# 13-JLINK_2.net
KiCad netlist of a schematic drawn in Altium Designer
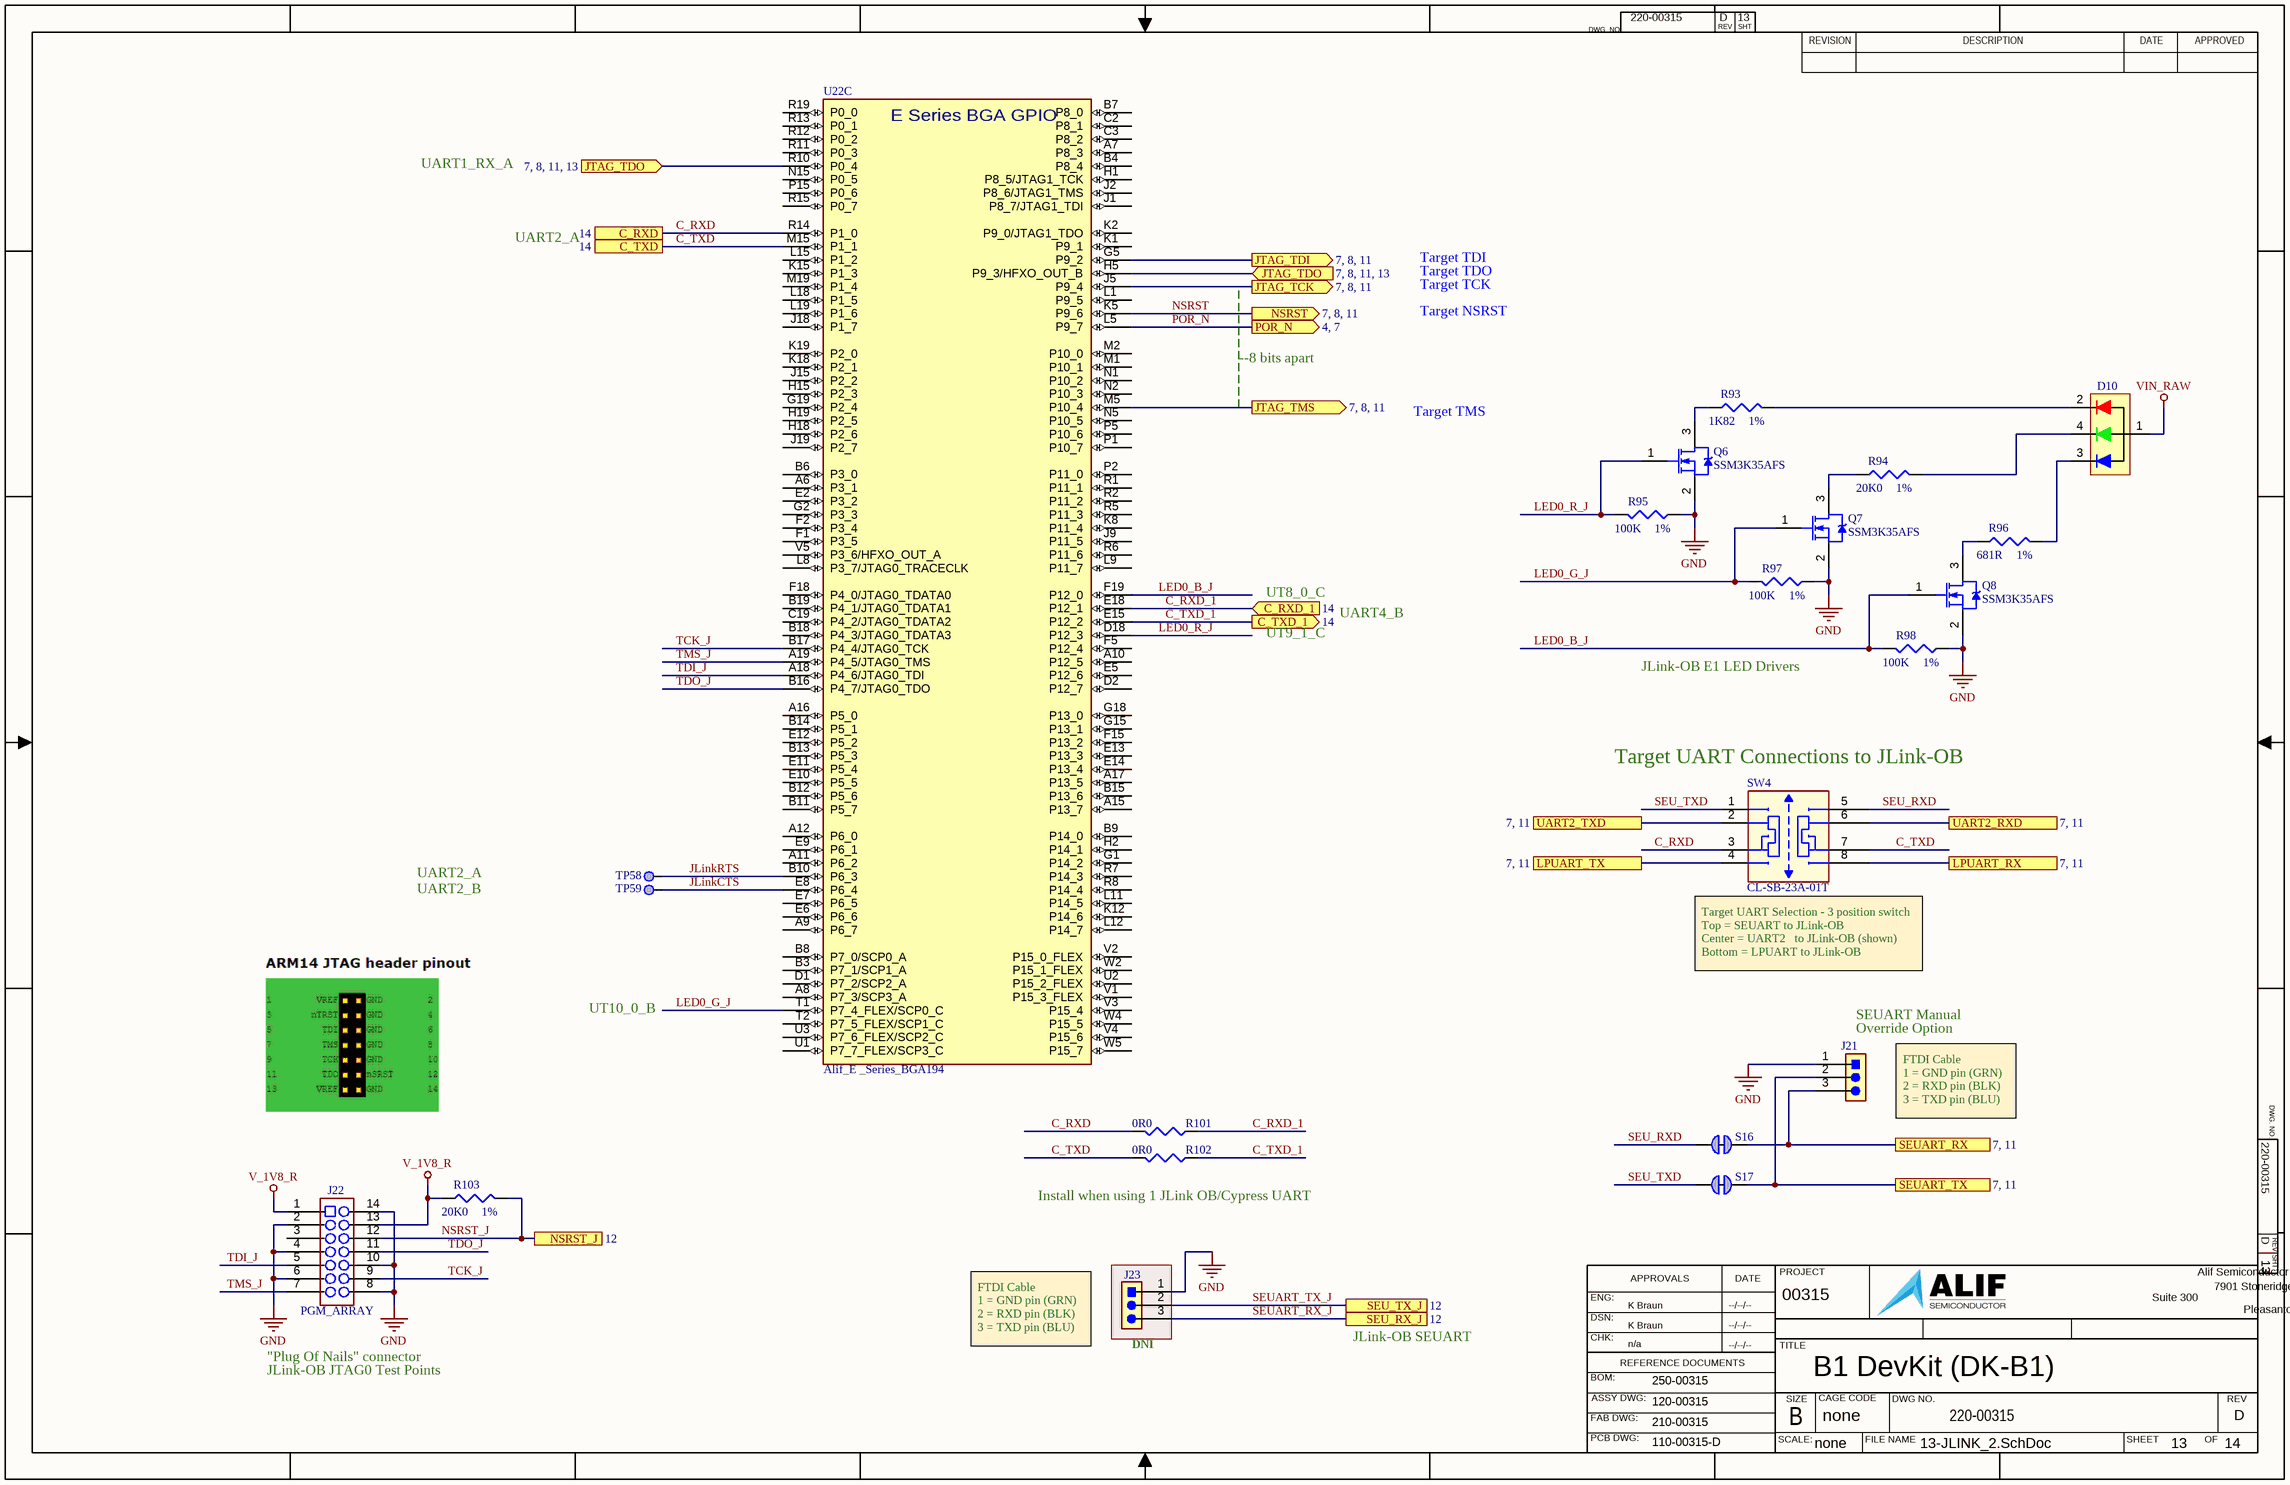
[diagram p0: 13-JLINK_2.SchDoc]

(export (version "E")
  (design (tool "Eeschema 10.0.6"))
  (components
    (comp (ref "D10")
      (value "SML-LX0404SIUPGUSB")
      (footprint "LED_SML-LX0404_LUM")
      (description "Diode,LED,RGB, (@2mA) -> R=10mcd & 1.75V, G = 50mcd & 2.75V, B = 20mcd & 2.95V, 0404(1mm x 1mm)")
      (fields (field (name "PUBLISHER") "Altium Limited"))
      (libsource (lib "Alif-2") (part "D LED_RGB_CA_1MMc1MM"))
    )
    (comp (ref "J21")
      (value "TSW-103-07-G-S")
      (footprint "CONN_HDR_1X3_STRT_0.100_no3D")
      (fields (field (name "MANUFACTURER") "Samtec"))
      (libsource (lib "") (part "Hdr_M_1X3_2M54_STRT_UNSHROUD_1"))
    )
    (comp (ref "J22")
      (value "PGM_ARRAY")
      (footprint "TC2070-IDC")
      (description "Test Point, Array, Alignment Pins, SMT Pad,--not a BOM item--")
      (fields (field (name "Comment") "PGMG_CONTACT,14P,TC2070-IDC_1"))
      (libsource (lib "Alif-2") (part "PGMG_CONTACT,14P,TC2070-IDC_1"))
    )
    (comp (ref "J23")
      (value "TSW-103-07-G-S")
      (footprint "CONN_HDR_1X3_STRT_0.100_no3D")
      (fields (field (name "MANUFACTURER") "Samtec"))
      (libsource (lib "Alif-2") (part "Hdr_M_1X3_2M54_STRT_UNSHROUD"))
    )
    (comp (ref "Q6")
      (value "NMOS-2_SOT")
      (footprint "SC75_SSM_TOS-L")
      (description "MOSFET,N-CH,20V,250mA,1.1Ohm,SOT-23")
      (fields
        (field (name "MANUFACTURER PART NUMBER 1") "SSM3K35AFS")
        (field (name "PUBLISHER") "Altium Limited")
      )
      (libsource (lib "Alif-2") (part "NMOS-2_SOT"))
    )
    (comp (ref "Q7")
      (value "NMOS-2_SOT")
      (footprint "SC75_SSM_TOS-L")
      (description "MOSFET,N-CH,20V,250mA,1.1Ohm,SOT-23")
      (fields
        (field (name "MANUFACTURER PART NUMBER 1") "SSM3K35AFS")
        (field (name "PUBLISHER") "Altium Limited")
      )
      (libsource (lib "Alif-2") (part "NMOS-2_SOT"))
    )
    (comp (ref "Q8")
      (value "NMOS-2_SOT")
      (footprint "SC75_SSM_TOS-L")
      (description "MOSFET,N-CH,20V,250mA,1.1Ohm,SOT-23")
      (fields
        (field (name "MANUFACTURER PART NUMBER 1") "SSM3K35AFS")
        (field (name "PUBLISHER") "Altium Limited")
      )
      (libsource (lib "Alif-2") (part "NMOS-2_SOT"))
    )
    (comp (ref "R93")
      (value "1K82")
      (footprint "RESC0402-01")
      (description "Res,1K82,1%,100ppm,0402")
      (fields
        (field (name "TOLERANCE") "1%")
        (field (name "Comment") "Res3")
        (field (name "PUBLISHER") "Altium Limited")
      )
      (libsource (lib "kb1") (part "Res3"))
    )
    (comp (ref "R94")
      (value "20K0")
      (footprint "RESC0402-01")
      (description "Res,20K0,1%,100ppm,0402")
      (fields
        (field (name "TOLERANCE") "1%")
        (field (name "Comment") "Res3")
        (field (name "PUBLISHER") "Altium Limited")
      )
      (libsource (lib "kb1") (part "Res3"))
    )
    (comp (ref "R95")
      (value "100K")
      (footprint "RESC0402-01")
      (description "Res,100K,1%,100ppm,0402")
      (fields
        (field (name "TOLERANCE") "1%")
        (field (name "Comment") "Res3")
        (field (name "PUBLISHER") "Altium Limited")
      )
      (libsource (lib "kb1") (part "Res3"))
    )
    (comp (ref "R96")
      (value "681R")
      (footprint "RESC0402-01")
      (description "Res,681R,1%,100ppm,0402")
      (fields
        (field (name "TOLERANCE") "1%")
        (field (name "Comment") "Res3")
        (field (name "PUBLISHER") "Altium Limited")
      )
      (libsource (lib "kb1") (part "Res3"))
    )
    (comp (ref "R97")
      (value "100K")
      (footprint "RESC0402-01")
      (description "Res,100K,1%,100ppm,0402")
      (fields
        (field (name "TOLERANCE") "1%")
        (field (name "Comment") "Res3")
        (field (name "PUBLISHER") "Altium Limited")
      )
      (libsource (lib "kb1") (part "Res3"))
    )
    (comp (ref "R98")
      (value "100K")
      (footprint "RESC0402-01")
      (description "Res,100K,1%,100ppm,0402")
      (fields
        (field (name "TOLERANCE") "1%")
        (field (name "Comment") "Res3")
        (field (name "PUBLISHER") "Altium Limited")
      )
      (libsource (lib "kb1") (part "Res3"))
    )
    (comp (ref "R101")
      (value "0R0")
      (footprint "RESC0402-01")
      (description "Res,0R ohm,Jumper,0402")
      (fields
        (field (name "TOLERANCE") "JMPR")
        (field (name "Comment") "Res3")
        (field (name "PUBLISHER") "Altium Limited")
      )
      (libsource (lib "kb1") (part "Res3"))
    )
    (comp (ref "R102")
      (value "0R0")
      (footprint "RESC0402-01")
      (description "Res,0R ohm,Jumper,0402")
      (fields
        (field (name "TOLERANCE") "JMPR")
        (field (name "Comment") "Res3")
        (field (name "PUBLISHER") "Altium Limited")
      )
      (libsource (lib "kb1") (part "Res3"))
    )
    (comp (ref "R103")
      (value "20K0")
      (footprint "RESC0402-01")
      (description "Res,20K0,1%,100ppm,0402")
      (fields
        (field (name "TOLERANCE") "1%")
        (field (name "Comment") "Res3")
        (field (name "PUBLISHER") "Altium Limited")
      )
      (libsource (lib "kb1") (part "Res3"))
    )
    (comp (ref "S16")
      (value "SolderJumperShorted_Small")
      (footprint "Solderbridge_Shorted")
      (description "DNI,Solderable Jumper,Shorted")
      (fields (field (name "PUBLISHER") "Altium Limited"))
      (libsource (lib "Alif-2") (part "SolderJumperShorted_Small"))
    )
    (comp (ref "S17")
      (value "SolderJumperShorted_Small")
      (footprint "Solderbridge_Shorted")
      (description "DNI,Solderable Jumper,Shorted")
      (fields (field (name "PUBLISHER") "Altium Limited"))
      (libsource (lib "Alif-2") (part "SolderJumperShorted_Small"))
    )
    (comp (ref "SW4")
      (value "CL-SB-23A-01T")
      (footprint "SW_CL-SB-23A-01_NDC-M")
      (description "Switch, DP3T Slide,8-pin, Vertical, 13mm x 3.6mm x 3.5mm, Actuator 2mm , Tin Contacts,JLead SMT")
      (libsource (lib "Alif-2") (part "SW_DP3T_CL-SB-23A-01T"))
    )
    (comp (ref "TP58")
      (value "TP_SMPAD")
      (footprint "TP_30_RND")
      (description "Test Point, SMT Pad,--not a BOM item--")
      (libsource (lib "Alif-2") (part "TP_SMPAD"))
    )
    (comp (ref "TP59")
      (value "TP_SMPAD")
      (footprint "TP_30_RND")
      (description "Test Point, SMT Pad,--not a BOM item--")
      (libsource (lib "Alif-2") (part "TP_SMPAD"))
    )
    (comp (ref "U22")
      (value "Alif_E _Series_BGA194")
      (footprint "BGA194 _CENTERED")
      (description "IC,Alif E1 MCU, Rev B silicon,BGA194")
      (libsource (lib "Alif") (part "E7_B0_194BGA"))
    )
  )
  (nets
    (net (code "1") (name "/C_RXD") (class "Default")
      (node (ref "R101") (pin "2") (pinfunction "2_2") (pintype "passive"))
      (node (ref "SW4") (pin "3") (pinfunction "CA_3") (pintype "passive"))
      (node (ref "U22") (pin "R14") (pinfunction "P1_0_R14") (pintype "bidirectional"))
    )
    (net (code "2") (name "/C_RXD_1") (class "Default")
      (node (ref "R101") (pin "1") (pinfunction "1_1") (pintype "passive"))
      (node (ref "U22") (pin "E18") (pinfunction "P12_1_E18") (pintype "bidirectional"))
    )
    (net (code "3") (name "/C_TXD") (class "Default")
      (node (ref "R102") (pin "2") (pinfunction "2_2") (pintype "passive"))
      (node (ref "SW4") (pin "7") (pinfunction "2B_7") (pintype "passive"))
      (node (ref "U22") (pin "M15") (pinfunction "P1_1_M15") (pintype "bidirectional"))
    )
    (net (code "4") (name "/C_TXD_1") (class "Default")
      (node (ref "R102") (pin "1") (pinfunction "1_1") (pintype "passive"))
      (node (ref "U22") (pin "E15") (pinfunction "P12_2_E15") (pintype "bidirectional"))
    )
    (net (code "5") (name "/JLinkCTS") (class "Default")
      (node (ref "TP59") (pin "1") (pinfunction "1_1") (pintype "passive"))
      (node (ref "U22") (pin "E8") (pinfunction "P6_4_E8") (pintype "bidirectional"))
    )
    (net (code "6") (name "/JLinkRTS") (class "Default")
      (node (ref "TP58") (pin "1") (pinfunction "1_1") (pintype "passive"))
      (node (ref "U22") (pin "B10") (pinfunction "P6_3_B10") (pintype "bidirectional"))
    )
    (net (code "7") (name "/JTAG_TCK") (class "Default")
      (node (ref "U22") (pin "J5") (pinfunction "P9_4_J5") (pintype "bidirectional"))
    )
    (net (code "8") (name "/JTAG_TDI") (class "Default")
      (node (ref "U22") (pin "G5") (pinfunction "P9_2_G5") (pintype "bidirectional"))
    )
    (net (code "9") (name "/JTAG_TDO") (class "Default")
      (node (ref "U22") (pin "H5") (pinfunction "P9_3/HFXO_OUT_B_H5") (pintype "bidirectional"))
      (node (ref "U22") (pin "R10") (pinfunction "P0_4_R10") (pintype "bidirectional"))
    )
    (net (code "10") (name "/JTAG_TMS") (class "Default")
      (node (ref "U22") (pin "M5") (pinfunction "P10_4_M5") (pintype "bidirectional"))
    )
    (net (code "11") (name "/LED0_B_J") (class "Default")
      (node (ref "Q8") (pin "1") (pinfunction "G_1") (pintype "passive"))
      (node (ref "R98") (pin "2") (pinfunction "2_2") (pintype "passive"))
      (node (ref "U22") (pin "F19") (pinfunction "P12_0_F19") (pintype "bidirectional"))
    )
    (net (code "12") (name "/LED0_G_J") (class "Default")
      (node (ref "Q7") (pin "1") (pinfunction "G_1") (pintype "passive"))
      (node (ref "R97") (pin "2") (pinfunction "2_2") (pintype "passive"))
      (node (ref "U22") (pin "T1") (pinfunction "P7_4_FLEX/SCP0_C_T1") (pintype "bidirectional"))
    )
    (net (code "13") (name "/LED0_R_J") (class "Default")
      (node (ref "Q6") (pin "1") (pinfunction "G_1") (pintype "passive"))
      (node (ref "R95") (pin "2") (pinfunction "2_2") (pintype "passive"))
      (node (ref "U22") (pin "D18") (pinfunction "P12_3_D18") (pintype "bidirectional"))
    )
    (net (code "14") (name "/LPUART_RX") (class "Default")
      (node (ref "SW4") (pin "8") (pinfunction "1B_8") (pintype "passive"))
    )
    (net (code "15") (name "/LPUART_TX") (class "Default")
      (node (ref "SW4") (pin "4") (pinfunction "3A_4") (pintype "passive"))
    )
    (net (code "16") (name "/NSRST") (class "Default")
      (node (ref "U22") (pin "K5") (pinfunction "P9_6_K5") (pintype "bidirectional"))
    )
    (net (code "17") (name "/NSRST_J") (class "Default")
      (node (ref "J22") (pin "12") (pinfunction "12_12") (pintype "passive"))
      (node (ref "R103") (pin "2") (pinfunction "2_2") (pintype "passive"))
    )
    (net (code "18") (name "/POR_N") (class "Default")
      (node (ref "U22") (pin "L5") (pinfunction "P9_7_L5") (pintype "bidirectional"))
    )
    (net (code "19") (name "/SEUART_RX") (class "Default")
      (node (ref "J21") (pin "3") (pinfunction "3_3") (pintype "passive"))
      (node (ref "S16") (pin "2") (pinfunction "2_2") (pintype "passive"))
    )
    (net (code "20") (name "/SEUART_RX_J") (class "Default")
      (node (ref "J23") (pin "3") (pinfunction "3_3") (pintype "passive"))
    )
    (net (code "21") (name "/SEUART_TX") (class "Default")
      (node (ref "J21") (pin "2") (pinfunction "2_2") (pintype "passive"))
      (node (ref "S17") (pin "2") (pinfunction "2_2") (pintype "passive"))
    )
    (net (code "22") (name "/SEUART_TX_J") (class "Default")
      (node (ref "J23") (pin "2") (pinfunction "2_2") (pintype "passive"))
    )
    (net (code "23") (name "/SEU_RXD") (class "Default")
      (node (ref "S16") (pin "1") (pinfunction "1_1") (pintype "passive"))
      (node (ref "SW4") (pin "5") (pinfunction "3B_5") (pintype "passive"))
    )
    (net (code "24") (name "/SEU_TXD") (class "Default")
      (node (ref "S17") (pin "1") (pinfunction "1_1") (pintype "passive"))
      (node (ref "SW4") (pin "1") (pinfunction "1A_1") (pintype "passive"))
    )
    (net (code "25") (name "/TCK_J") (class "Default")
      (node (ref "J22") (pin "9") (pinfunction "9_9") (pintype "passive"))
      (node (ref "U22") (pin "B17") (pinfunction "P4_4/JTAG0_TCK_B17") (pintype "bidirectional"))
    )
    (net (code "26") (name "/TDI_J") (class "Default")
      (node (ref "J22") (pin "5") (pinfunction "5_5") (pintype "passive"))
      (node (ref "U22") (pin "A18") (pinfunction "P4_6/JTAG0_TDI_A18") (pintype "bidirectional"))
    )
    (net (code "27") (name "/TDO_J") (class "Default")
      (node (ref "J22") (pin "11") (pinfunction "11_11") (pintype "passive"))
      (node (ref "U22") (pin "B16") (pinfunction "P4_7/JTAG0_TDO_B16") (pintype "bidirectional"))
    )
    (net (code "28") (name "/TMS_J") (class "Default")
      (node (ref "J22") (pin "7") (pinfunction "7_7") (pintype "passive"))
      (node (ref "U22") (pin "A19") (pinfunction "P4_5/JTAG0_TMS_A19") (pintype "bidirectional"))
    )
    (net (code "29") (name "/UART2_RXD") (class "Default")
      (node (ref "SW4") (pin "6") (pinfunction "CB_6") (pintype "passive"))
    )
    (net (code "30") (name "/UART2_TXD") (class "Default")
      (node (ref "SW4") (pin "2") (pinfunction "2A_2") (pintype "passive"))
    )
    (net (code "31") (name "GND") (class "Default")
      (node (ref "J21") (pin "1") (pinfunction "1_1") (pintype "passive"))
      (node (ref "J22") (pin "10") (pinfunction "10_10") (pintype "passive"))
      (node (ref "J22") (pin "14") (pinfunction "14_14") (pintype "passive"))
      (node (ref "J22") (pin "2") (pinfunction "2_2") (pintype "passive"))
      (node (ref "J22") (pin "4") (pinfunction "4_4") (pintype "passive"))
      (node (ref "J22") (pin "6") (pinfunction "6_6") (pintype "passive"))
      (node (ref "J22") (pin "8") (pinfunction "8_8") (pintype "passive"))
      (node (ref "J23") (pin "1") (pinfunction "1_1") (pintype "passive"))
      (node (ref "Q6") (pin "2") (pinfunction "S_2") (pintype "passive"))
      (node (ref "Q7") (pin "2") (pinfunction "S_2") (pintype "passive"))
      (node (ref "Q8") (pin "2") (pinfunction "S_2") (pintype "passive"))
      (node (ref "R95") (pin "1") (pinfunction "1_1") (pintype "passive"))
      (node (ref "R97") (pin "1") (pinfunction "1_1") (pintype "passive"))
      (node (ref "R98") (pin "1") (pinfunction "1_1") (pintype "passive"))
    )
    (net (code "32") (name "Net-(D10-BK)") (class "Default")
      (node (ref "D10") (pin "3") (pinfunction "BK_3") (pintype "passive"))
      (node (ref "R96") (pin "2") (pinfunction "2_2") (pintype "passive"))
    )
    (net (code "33") (name "Net-(D10-GK)") (class "Default")
      (node (ref "D10") (pin "4") (pinfunction "GK_4") (pintype "passive"))
      (node (ref "R94") (pin "2") (pinfunction "2_2") (pintype "passive"))
    )
    (net (code "34") (name "Net-(D10-RK)") (class "Default")
      (node (ref "D10") (pin "2") (pinfunction "RK_2") (pintype "passive"))
      (node (ref "R93") (pin "2") (pinfunction "2_2") (pintype "passive"))
    )
    (net (code "35") (name "Net-(Q6-D)") (class "Default")
      (node (ref "Q6") (pin "3") (pinfunction "D_3") (pintype "passive"))
      (node (ref "R93") (pin "1") (pinfunction "1_1") (pintype "passive"))
    )
    (net (code "36") (name "Net-(Q7-D)") (class "Default")
      (node (ref "Q7") (pin "3") (pinfunction "D_3") (pintype "passive"))
      (node (ref "R94") (pin "1") (pinfunction "1_1") (pintype "passive"))
    )
    (net (code "37") (name "Net-(Q8-D)") (class "Default")
      (node (ref "Q8") (pin "3") (pinfunction "D_3") (pintype "passive"))
      (node (ref "R96") (pin "1") (pinfunction "1_1") (pintype "passive"))
    )
    (net (code "38") (name "VIN_RAW") (class "Default")
      (node (ref "D10") (pin "1") (pinfunction "A_1") (pintype "passive"))
    )
    (net (code "39") (name "V_1V8_R") (class "Default")
      (node (ref "J22") (pin "1") (pinfunction "1_1") (pintype "passive"))
      (node (ref "J22") (pin "13") (pinfunction "13_13") (pintype "passive"))
      (node (ref "R103") (pin "1") (pinfunction "1_1") (pintype "passive"))
    )
    (net (code "40") (name "unconnected-(J22-Pad3)") (class "Default")
      (node (ref "J22") (pin "3") (pinfunction "3_3") (pintype "passive"))
    )
    (net (code "41") (name "unconnected-(U22C-P0_0-PadR19)") (class "Default")
      (node (ref "U22") (pin "R19") (pinfunction "P0_0_R19") (pintype "bidirectional"))
    )
    (net (code "42") (name "unconnected-(U22C-P0_1-PadR13)") (class "Default")
      (node (ref "U22") (pin "R13") (pinfunction "P0_1_R13") (pintype "bidirectional"))
    )
    (net (code "43") (name "unconnected-(U22C-P0_2-PadR12)") (class "Default")
      (node (ref "U22") (pin "R12") (pinfunction "P0_2_R12") (pintype "bidirectional"))
    )
    (net (code "44") (name "unconnected-(U22C-P0_3-PadR11)") (class "Default")
      (node (ref "U22") (pin "R11") (pinfunction "P0_3_R11") (pintype "bidirectional"))
    )
    (net (code "45") (name "unconnected-(U22C-P0_5-PadN15)") (class "Default")
      (node (ref "U22") (pin "N15") (pinfunction "P0_5_N15") (pintype "bidirectional"))
    )
    (net (code "46") (name "unconnected-(U22C-P0_6-PadP15)") (class "Default")
      (node (ref "U22") (pin "P15") (pinfunction "P0_6_P15") (pintype "bidirectional"))
    )
    (net (code "47") (name "unconnected-(U22C-P0_7-PadR15)") (class "Default")
      (node (ref "U22") (pin "R15") (pinfunction "P0_7_R15") (pintype "bidirectional"))
    )
    (net (code "48") (name "unconnected-(U22C-P1_2-PadL15)") (class "Default")
      (node (ref "U22") (pin "L15") (pinfunction "P1_2_L15") (pintype "bidirectional"))
    )
    (net (code "49") (name "unconnected-(U22C-P1_3-PadK15)") (class "Default")
      (node (ref "U22") (pin "K15") (pinfunction "P1_3_K15") (pintype "bidirectional"))
    )
    (net (code "50") (name "unconnected-(U22C-P1_4-PadM19)") (class "Default")
      (node (ref "U22") (pin "M19") (pinfunction "P1_4_M19") (pintype "bidirectional"))
    )
    (net (code "51") (name "unconnected-(U22C-P1_5-PadL18)") (class "Default")
      (node (ref "U22") (pin "L18") (pinfunction "P1_5_L18") (pintype "bidirectional"))
    )
    (net (code "52") (name "unconnected-(U22C-P1_6-PadL19)") (class "Default")
      (node (ref "U22") (pin "L19") (pinfunction "P1_6_L19") (pintype "bidirectional"))
    )
    (net (code "53") (name "unconnected-(U22C-P1_7-PadJ18)") (class "Default")
      (node (ref "U22") (pin "J18") (pinfunction "P1_7_J18") (pintype "bidirectional"))
    )
    (net (code "54") (name "unconnected-(U22C-P2_0-PadK19)") (class "Default")
      (node (ref "U22") (pin "K19") (pinfunction "P2_0_K19") (pintype "bidirectional"))
    )
    (net (code "55") (name "unconnected-(U22C-P2_1-PadK18)") (class "Default")
      (node (ref "U22") (pin "K18") (pinfunction "P2_1_K18") (pintype "bidirectional"))
    )
    (net (code "56") (name "unconnected-(U22C-P2_2-PadJ15)") (class "Default")
      (node (ref "U22") (pin "J15") (pinfunction "P2_2_J15") (pintype "bidirectional"))
    )
    (net (code "57") (name "unconnected-(U22C-P2_3-PadH15)") (class "Default")
      (node (ref "U22") (pin "H15") (pinfunction "P2_3_H15") (pintype "bidirectional"))
    )
    (net (code "58") (name "unconnected-(U22C-P2_4-PadG19)") (class "Default")
      (node (ref "U22") (pin "G19") (pinfunction "P2_4_G19") (pintype "bidirectional"))
    )
    (net (code "59") (name "unconnected-(U22C-P2_5-PadH19)") (class "Default")
      (node (ref "U22") (pin "H19") (pinfunction "P2_5_H19") (pintype "bidirectional"))
    )
    (net (code "60") (name "unconnected-(U22C-P2_6-PadH18)") (class "Default")
      (node (ref "U22") (pin "H18") (pinfunction "P2_6_H18") (pintype "bidirectional"))
    )
    (net (code "61") (name "unconnected-(U22C-P2_7-PadJ19)") (class "Default")
      (node (ref "U22") (pin "J19") (pinfunction "P2_7_J19") (pintype "bidirectional"))
    )
    (net (code "62") (name "unconnected-(U22C-P3_0-PadB6)") (class "Default")
      (node (ref "U22") (pin "B6") (pinfunction "P3_0_B6") (pintype "bidirectional"))
    )
    (net (code "63") (name "unconnected-(U22C-P3_1-PadA6)") (class "Default")
      (node (ref "U22") (pin "A6") (pinfunction "P3_1_A6") (pintype "bidirectional"))
    )
    (net (code "64") (name "unconnected-(U22C-P3_2-PadE2)") (class "Default")
      (node (ref "U22") (pin "E2") (pinfunction "P3_2_E2") (pintype "bidirectional"))
    )
    (net (code "65") (name "unconnected-(U22C-P3_3-PadG2)") (class "Default")
      (node (ref "U22") (pin "G2") (pinfunction "P3_3_G2") (pintype "bidirectional"))
    )
    (net (code "66") (name "unconnected-(U22C-P3_4-PadF2)") (class "Default")
      (node (ref "U22") (pin "F2") (pinfunction "P3_4_F2") (pintype "bidirectional"))
    )
    (net (code "67") (name "unconnected-(U22C-P3_5-PadF1)") (class "Default")
      (node (ref "U22") (pin "F1") (pinfunction "P3_5_F1") (pintype "bidirectional"))
    )
    (net (code "68") (name "unconnected-(U22C-P3_6{slash}HFXO_OUT_A-PadV5)") (class "Default")
      (node (ref "U22") (pin "V5") (pinfunction "P3_6/HFXO_OUT_A_V5") (pintype "bidirectional"))
    )
    (net (code "69") (name "unconnected-(U22C-P3_7{slash}JTAG0_TRACECLK-PadL8)") (class "Default")
      (node (ref "U22") (pin "L8") (pinfunction "P3_7/JTAG0_TRACECLK_L8") (pintype "bidirectional"))
    )
    (net (code "70") (name "unconnected-(U22C-P4_0{slash}JTAG0_TDATA0-PadF18)") (class "Default")
      (node (ref "U22") (pin "F18") (pinfunction "P4_0/JTAG0_TDATA0_F18") (pintype "bidirectional"))
    )
    (net (code "71") (name "unconnected-(U22C-P4_1{slash}JTAG0_TDATA1-PadB19)") (class "Default")
      (node (ref "U22") (pin "B19") (pinfunction "P4_1/JTAG0_TDATA1_B19") (pintype "bidirectional"))
    )
    (net (code "72") (name "unconnected-(U22C-P4_2{slash}JTAG0_TDATA2-PadC19)") (class "Default")
      (node (ref "U22") (pin "C19") (pinfunction "P4_2/JTAG0_TDATA2_C19") (pintype "bidirectional"))
    )
    (net (code "73") (name "unconnected-(U22C-P4_3{slash}JTAG0_TDATA3-PadB18)") (class "Default")
      (node (ref "U22") (pin "B18") (pinfunction "P4_3/JTAG0_TDATA3_B18") (pintype "bidirectional"))
    )
    (net (code "74") (name "unconnected-(U22C-P5_0-PadA16)") (class "Default")
      (node (ref "U22") (pin "A16") (pinfunction "P5_0_A16") (pintype "bidirectional"))
    )
    (net (code "75") (name "unconnected-(U22C-P5_1-PadB14)") (class "Default")
      (node (ref "U22") (pin "B14") (pinfunction "P5_1_B14") (pintype "bidirectional"))
    )
    (net (code "76") (name "unconnected-(U22C-P5_2-PadE12)") (class "Default")
      (node (ref "U22") (pin "E12") (pinfunction "P5_2_E12") (pintype "bidirectional"))
    )
    (net (code "77") (name "unconnected-(U22C-P5_3-PadB13)") (class "Default")
      (node (ref "U22") (pin "B13") (pinfunction "P5_3_B13") (pintype "bidirectional"))
    )
    (net (code "78") (name "unconnected-(U22C-P5_4-PadE11)") (class "Default")
      (node (ref "U22") (pin "E11") (pinfunction "P5_4_E11") (pintype "bidirectional"))
    )
    (net (code "79") (name "unconnected-(U22C-P5_5-PadE10)") (class "Default")
      (node (ref "U22") (pin "E10") (pinfunction "P5_5_E10") (pintype "bidirectional"))
    )
    (net (code "80") (name "unconnected-(U22C-P5_6-PadB12)") (class "Default")
      (node (ref "U22") (pin "B12") (pinfunction "P5_6_B12") (pintype "bidirectional"))
    )
    (net (code "81") (name "unconnected-(U22C-P5_7-PadB11)") (class "Default")
      (node (ref "U22") (pin "B11") (pinfunction "P5_7_B11") (pintype "bidirectional"))
    )
    (net (code "82") (name "unconnected-(U22C-P6_0-PadA12)") (class "Default")
      (node (ref "U22") (pin "A12") (pinfunction "P6_0_A12") (pintype "bidirectional"))
    )
    (net (code "83") (name "unconnected-(U22C-P6_1-PadE9)") (class "Default")
      (node (ref "U22") (pin "E9") (pinfunction "P6_1_E9") (pintype "bidirectional"))
    )
    (net (code "84") (name "unconnected-(U22C-P6_2-PadA11)") (class "Default")
      (node (ref "U22") (pin "A11") (pinfunction "P6_2_A11") (pintype "bidirectional"))
    )
    (net (code "85") (name "unconnected-(U22C-P6_5-PadE7)") (class "Default")
      (node (ref "U22") (pin "E7") (pinfunction "P6_5_E7") (pintype "bidirectional"))
    )
    (net (code "86") (name "unconnected-(U22C-P6_6-PadE6)") (class "Default")
      (node (ref "U22") (pin "E6") (pinfunction "P6_6_E6") (pintype "bidirectional"))
    )
    (net (code "87") (name "unconnected-(U22C-P6_7-PadA9)") (class "Default")
      (node (ref "U22") (pin "A9") (pinfunction "P6_7_A9") (pintype "bidirectional"))
    )
    (net (code "88") (name "unconnected-(U22C-P7_0{slash}SCP0_A-PadB8)") (class "Default")
      (node (ref "U22") (pin "B8") (pinfunction "P7_0/SCP0_A_B8") (pintype "bidirectional"))
    )
    (net (code "89") (name "unconnected-(U22C-P7_1{slash}SCP1_A-PadB3)") (class "Default")
      (node (ref "U22") (pin "B3") (pinfunction "P7_1/SCP1_A_B3") (pintype "bidirectional"))
    )
    (net (code "90") (name "unconnected-(U22C-P7_2{slash}SCP2_A-PadD1)") (class "Default")
      (node (ref "U22") (pin "D1") (pinfunction "P7_2/SCP2_A_D1") (pintype "bidirectional"))
    )
    (net (code "91") (name "unconnected-(U22C-P7_3{slash}SCP3_A-PadA8)") (class "Default")
      (node (ref "U22") (pin "A8") (pinfunction "P7_3/SCP3_A_A8") (pintype "bidirectional"))
    )
    (net (code "92") (name "unconnected-(U22C-P7_5_FLEX{slash}SCP1_C-PadT2)") (class "Default")
      (node (ref "U22") (pin "T2") (pinfunction "P7_5_FLEX/SCP1_C_T2") (pintype "bidirectional"))
    )
    (net (code "93") (name "unconnected-(U22C-P7_6_FLEX{slash}SCP2_C-PadU3)") (class "Default")
      (node (ref "U22") (pin "U3") (pinfunction "P7_6_FLEX/SCP2_C_U3") (pintype "bidirectional"))
    )
    (net (code "94") (name "unconnected-(U22C-P7_7_FLEX{slash}SCP3_C-PadU1)") (class "Default")
      (node (ref "U22") (pin "U1") (pinfunction "P7_7_FLEX/SCP3_C_U1") (pintype "bidirectional"))
    )
    (net (code "95") (name "unconnected-(U22C-P8_0-PadB7)") (class "Default")
      (node (ref "U22") (pin "B7") (pinfunction "P8_0_B7") (pintype "bidirectional"))
    )
    (net (code "96") (name "unconnected-(U22C-P8_1-PadC2)") (class "Default")
      (node (ref "U22") (pin "C2") (pinfunction "P8_1_C2") (pintype "bidirectional"))
    )
    (net (code "97") (name "unconnected-(U22C-P8_2-PadC3)") (class "Default")
      (node (ref "U22") (pin "C3") (pinfunction "P8_2_C3") (pintype "bidirectional"))
    )
    (net (code "98") (name "unconnected-(U22C-P8_3-PadA7)") (class "Default")
      (node (ref "U22") (pin "A7") (pinfunction "P8_3_A7") (pintype "bidirectional"))
    )
    (net (code "99") (name "unconnected-(U22C-P8_4-PadB4)") (class "Default")
      (node (ref "U22") (pin "B4") (pinfunction "P8_4_B4") (pintype "bidirectional"))
    )
    (net (code "100") (name "unconnected-(U22C-P8_5{slash}JTAG1_TCK-PadH1)") (class "Default")
      (node (ref "U22") (pin "H1") (pinfunction "P8_5/JTAG1_TCK_H1") (pintype "bidirectional"))
    )
    (net (code "101") (name "unconnected-(U22C-P8_6{slash}JTAG1_TMS-PadJ2)") (class "Default")
      (node (ref "U22") (pin "J2") (pinfunction "P8_6/JTAG1_TMS_J2") (pintype "bidirectional"))
    )
    (net (code "102") (name "unconnected-(U22C-P8_7{slash}JTAG1_TDI-PadJ1)") (class "Default")
      (node (ref "U22") (pin "J1") (pinfunction "P8_7/JTAG1_TDI_J1") (pintype "bidirectional"))
    )
    (net (code "103") (name "unconnected-(U22C-P9_0{slash}JTAG1_TDO-PadK2)") (class "Default")
      (node (ref "U22") (pin "K2") (pinfunction "P9_0/JTAG1_TDO_K2") (pintype "bidirectional"))
    )
    (net (code "104") (name "unconnected-(U22C-P9_1-PadK1)") (class "Default")
      (node (ref "U22") (pin "K1") (pinfunction "P9_1_K1") (pintype "bidirectional"))
    )
    (net (code "105") (name "unconnected-(U22C-P9_5-PadL1)") (class "Default")
      (node (ref "U22") (pin "L1") (pinfunction "P9_5_L1") (pintype "bidirectional"))
    )
    (net (code "106") (name "unconnected-(U22C-P10_0-PadM2)") (class "Default")
      (node (ref "U22") (pin "M2") (pinfunction "P10_0_M2") (pintype "bidirectional"))
    )
    (net (code "107") (name "unconnected-(U22C-P10_1-PadM1)") (class "Default")
      (node (ref "U22") (pin "M1") (pinfunction "P10_1_M1") (pintype "bidirectional"))
    )
    (net (code "108") (name "unconnected-(U22C-P10_2-PadN1)") (class "Default")
      (node (ref "U22") (pin "N1") (pinfunction "P10_2_N1") (pintype "bidirectional"))
    )
    (net (code "109") (name "unconnected-(U22C-P10_3-PadN2)") (class "Default")
      (node (ref "U22") (pin "N2") (pinfunction "P10_3_N2") (pintype "bidirectional"))
    )
    (net (code "110") (name "unconnected-(U22C-P10_5-PadN5)") (class "Default")
      (node (ref "U22") (pin "N5") (pinfunction "P10_5_N5") (pintype "bidirectional"))
    )
    (net (code "111") (name "unconnected-(U22C-P10_6-PadP5)") (class "Default")
      (node (ref "U22") (pin "P5") (pinfunction "P10_6_P5") (pintype "bidirectional"))
    )
    (net (code "112") (name "unconnected-(U22C-P10_7-PadP1)") (class "Default")
      (node (ref "U22") (pin "P1") (pinfunction "P10_7_P1") (pintype "bidirectional"))
    )
    (net (code "113") (name "unconnected-(U22C-P11_0-PadP2)") (class "Default")
      (node (ref "U22") (pin "P2") (pinfunction "P11_0_P2") (pintype "bidirectional"))
    )
    (net (code "114") (name "unconnected-(U22C-P11_1-PadR1)") (class "Default")
      (node (ref "U22") (pin "R1") (pinfunction "P11_1_R1") (pintype "bidirectional"))
    )
    (net (code "115") (name "unconnected-(U22C-P11_2-PadR2)") (class "Default")
      (node (ref "U22") (pin "R2") (pinfunction "P11_2_R2") (pintype "bidirectional"))
    )
    (net (code "116") (name "unconnected-(U22C-P11_3-PadR5)") (class "Default")
      (node (ref "U22") (pin "R5") (pinfunction "P11_3_R5") (pintype "bidirectional"))
    )
    (net (code "117") (name "unconnected-(U22C-P11_4-PadK8)") (class "Default")
      (node (ref "U22") (pin "K8") (pinfunction "P11_4_K8") (pintype "bidirectional"))
    )
    (net (code "118") (name "unconnected-(U22C-P11_5-PadJ9)") (class "Default")
      (node (ref "U22") (pin "J9") (pinfunction "P11_5_J9") (pintype "bidirectional"))
    )
    (net (code "119") (name "unconnected-(U22C-P11_6-PadR6)") (class "Default")
      (node (ref "U22") (pin "R6") (pinfunction "P11_6_R6") (pintype "bidirectional"))
    )
    (net (code "120") (name "unconnected-(U22C-P11_7-PadL9)") (class "Default")
      (node (ref "U22") (pin "L9") (pinfunction "P11_7_L9") (pintype "bidirectional"))
    )
    (net (code "121") (name "unconnected-(U22C-P12_4-PadF5)") (class "Default")
      (node (ref "U22") (pin "F5") (pinfunction "P12_4_F5") (pintype "bidirectional"))
    )
    (net (code "122") (name "unconnected-(U22C-P12_5-PadA10)") (class "Default")
      (node (ref "U22") (pin "A10") (pinfunction "P12_5_A10") (pintype "bidirectional"))
    )
    (net (code "123") (name "unconnected-(U22C-P12_6-PadE5)") (class "Default")
      (node (ref "U22") (pin "E5") (pinfunction "P12_6_E5") (pintype "bidirectional"))
    )
    (net (code "124") (name "unconnected-(U22C-P12_7-PadD2)") (class "Default")
      (node (ref "U22") (pin "D2") (pinfunction "P12_7_D2") (pintype "bidirectional"))
    )
    (net (code "125") (name "unconnected-(U22C-P13_0-PadG18)") (class "Default")
      (node (ref "U22") (pin "G18") (pinfunction "P13_0_G18") (pintype "bidirectional"))
    )
    (net (code "126") (name "unconnected-(U22C-P13_1-PadG15)") (class "Default")
      (node (ref "U22") (pin "G15") (pinfunction "P13_1_G15") (pintype "bidirectional"))
    )
    (net (code "127") (name "unconnected-(U22C-P13_2-PadF15)") (class "Default")
      (node (ref "U22") (pin "F15") (pinfunction "P13_2_F15") (pintype "bidirectional"))
    )
    (net (code "128") (name "unconnected-(U22C-P13_3-PadE13)") (class "Default")
      (node (ref "U22") (pin "E13") (pinfunction "P13_3_E13") (pintype "bidirectional"))
    )
    (net (code "129") (name "unconnected-(U22C-P13_4-PadE14)") (class "Default")
      (node (ref "U22") (pin "E14") (pinfunction "P13_4_E14") (pintype "bidirectional"))
    )
    (net (code "130") (name "unconnected-(U22C-P13_5-PadA17)") (class "Default")
      (node (ref "U22") (pin "A17") (pinfunction "P13_5_A17") (pintype "bidirectional"))
    )
    (net (code "131") (name "unconnected-(U22C-P13_6-PadB15)") (class "Default")
      (node (ref "U22") (pin "B15") (pinfunction "P13_6_B15") (pintype "bidirectional"))
    )
    (net (code "132") (name "unconnected-(U22C-P13_7-PadA15)") (class "Default")
      (node (ref "U22") (pin "A15") (pinfunction "P13_7_A15") (pintype "bidirectional"))
    )
    (net (code "133") (name "unconnected-(U22C-P14_0-PadB9)") (class "Default")
      (node (ref "U22") (pin "B9") (pinfunction "P14_0_B9") (pintype "bidirectional"))
    )
    (net (code "134") (name "unconnected-(U22C-P14_1-PadH2)") (class "Default")
      (node (ref "U22") (pin "H2") (pinfunction "P14_1_H2") (pintype "bidirectional"))
    )
    (net (code "135") (name "unconnected-(U22C-P14_2-PadG1)") (class "Default")
      (node (ref "U22") (pin "G1") (pinfunction "P14_2_G1") (pintype "bidirectional"))
    )
    (net (code "136") (name "unconnected-(U22C-P14_3-PadR7)") (class "Default")
      (node (ref "U22") (pin "R7") (pinfunction "P14_3_R7") (pintype "bidirectional"))
    )
    (net (code "137") (name "unconnected-(U22C-P14_4-PadR8)") (class "Default")
      (node (ref "U22") (pin "R8") (pinfunction "P14_4_R8") (pintype "bidirectional"))
    )
    (net (code "138") (name "unconnected-(U22C-P14_5-PadL11)") (class "Default")
      (node (ref "U22") (pin "L11") (pinfunction "P14_5_L11") (pintype "bidirectional"))
    )
    (net (code "139") (name "unconnected-(U22C-P14_6-PadK12)") (class "Default")
      (node (ref "U22") (pin "K12") (pinfunction "P14_6_K12") (pintype "bidirectional"))
    )
    (net (code "140") (name "unconnected-(U22C-P14_7-PadL12)") (class "Default")
      (node (ref "U22") (pin "L12") (pinfunction "P14_7_L12") (pintype "bidirectional"))
    )
    (net (code "141") (name "unconnected-(U22C-P15_0_FLEX-PadV2)") (class "Default")
      (node (ref "U22") (pin "V2") (pinfunction "P15_0_FLEX_V2") (pintype "bidirectional"))
    )
    (net (code "142") (name "unconnected-(U22C-P15_1_FLEX-PadW2)") (class "Default")
      (node (ref "U22") (pin "W2") (pinfunction "P15_1_FLEX_W2") (pintype "bidirectional"))
    )
    (net (code "143") (name "unconnected-(U22C-P15_2_FLEX-PadU2)") (class "Default")
      (node (ref "U22") (pin "U2") (pinfunction "P15_2_FLEX_U2") (pintype "bidirectional"))
    )
    (net (code "144") (name "unconnected-(U22C-P15_3_FLEX-PadV1)") (class "Default")
      (node (ref "U22") (pin "V1") (pinfunction "P15_3_FLEX_V1") (pintype "bidirectional"))
    )
    (net (code "145") (name "unconnected-(U22C-P15_4-PadV3)") (class "Default")
      (node (ref "U22") (pin "V3") (pinfunction "P15_4_V3") (pintype "bidirectional"))
    )
    (net (code "146") (name "unconnected-(U22C-P15_5-PadW4)") (class "Default")
      (node (ref "U22") (pin "W4") (pinfunction "P15_5_W4") (pintype "bidirectional"))
    )
    (net (code "147") (name "unconnected-(U22C-P15_6-PadV4)") (class "Default")
      (node (ref "U22") (pin "V4") (pinfunction "P15_6_V4") (pintype "bidirectional"))
    )
    (net (code "148") (name "unconnected-(U22C-P15_7-PadW5)") (class "Default")
      (node (ref "U22") (pin "W5") (pinfunction "P15_7_W5") (pintype "bidirectional"))
    )
  )
)
